# ESP32_Power.net
KiCad netlist of a schematic drawn in Altium Designer
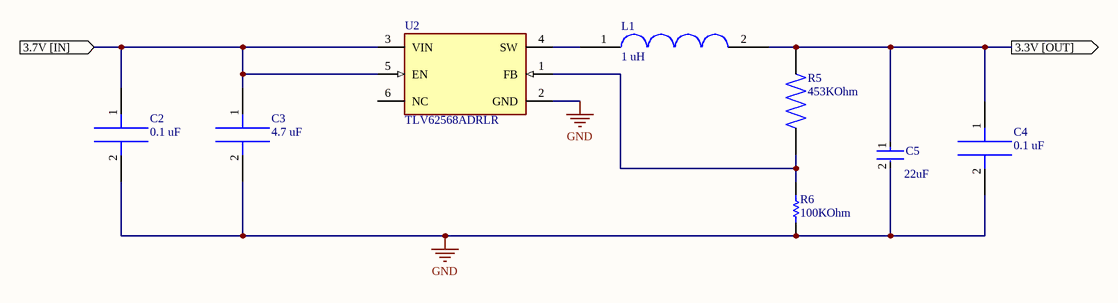
[diagram p0: ESP32 Power.SchDoc]

(export (version "E")
  (design (tool "Eeschema 10.0.6"))
  (components
    (comp (ref "C2")
      (value "0.1 uF")
      (footprint "1206 Capacitor")
      (description "0.1 µF ±10% 6.3V Ceramic Capacitor X7R 1206 (3216 Metric)")
      (fields (field (name "Comment") "GMC31X7R104K6R3NT"))
      (libsource (lib "Team54_Parts") (part "GMC31X7R104K6R3NT"))
    )
    (comp (ref "C3")
      (value "4.7 uF")
      (footprint "12101C47")
      (description "CAP CER 4.7UF 100V X7R 1210")
      (fields (field (name "Comment") "12101C475K4T2A"))
      (libsource (lib "Team54_Parts") (part "12101C47"))
    )
    (comp (ref "C4")
      (value "0.1 uF")
      (footprint "1206 Capacitor")
      (description "0.1 µF ±10% 6.3V Ceramic Capacitor X7R 1206 (3216 Metric)")
      (fields (field (name "Comment") "GMC31X7R104K6R3NT"))
      (libsource (lib "Team54_Parts") (part "GMC31X7R104K6R3NT"))
    )
    (comp (ref "C5")
      (value "GRM21BR60J226ME39L")
      (footprint "FP-GRM21B-0_15-MFG")
      (description "Chip Multilayer Ceramic Capacitors for General Purpose, 0805, 22uF, X5R, 15%, 20%, 6.3V")
      (fields
        (field (name "VOLTAGE") "6.3V")
        (field (name "TOLERANCE") "20%")
        (field (name "CAPACITANCE") "22uF")
      )
      (libsource (lib "Altium Content Vault") (part "b4654b650e69147ec39a6b967a45e02"))
    )
    (comp (ref "L1")
      (value "1 uH")
      (footprint "TYA40121R0M-10")
      (description "TYA40121R0M-10, FIXED IND 1UH 3A 59 MOHM SMD")
      (libsource (lib "Team54_Parts") (part "TYA40121R0M-10"))
    )
    (comp (ref "R5")
      (value "453KOhm")
      (footprint "RES_ERJP14F4533U")
      (description "ERJP14F4533U")
      (libsource (lib "ERJP14F4533U") (part "ERJP14F4533U"))
    )
    (comp (ref "R6")
      (value "RC1206FR-07100KL")
      (footprint "RESC3116X65X40ML10T20")
      (description "Chip Resistor, 100 KOhm, +/- 1%, 0.25 W, -55 to 155 degC, 1206 (3216 Metric), RoHS, Tape and Reel")
      (fields
        (field (name "RESISTANCE") "100KOhm")
        (field (name "TOLERANCE") "1%")
        (field (name "MANUFACTURER") "Yageo")
      )
      (libsource (lib "Altium Content Vault") (part "RES-2"))
    )
    (comp (ref "U2")
      (value "TLV62568ADRLR")
      (footprint "FP-DRL0006A-MFG")
      (description "IC REG BUCK ADJUSTABLE 2A SOT563")
      (libsource (lib "Altium Content Vault") (part "c065b8f3016c1e0e14a773cb518fcf3"))
    )
  )
  (nets
    (net (code "1") (name "/3.3V [OUT]") (class "Default")
      (node (ref "C4") (pin "1") (pinfunction "1_1") (pintype "passive"))
      (node (ref "C5") (pin "1") (pinfunction "1_1") (pintype "passive"))
      (node (ref "L1") (pin "2") (pinfunction "2_2") (pintype "passive"))
      (node (ref "R5") (pin "2") (pinfunction "2_2") (pintype "passive"))
    )
    (net (code "2") (name "/3.7V [IN]") (class "Default")
      (node (ref "C2") (pin "1") (pinfunction "1_1") (pintype "passive"))
      (node (ref "C3") (pin "1") (pinfunction "1_1") (pintype "passive"))
      (node (ref "U2") (pin "3") (pinfunction "VIN_3") (pintype "power_in"))
      (node (ref "U2") (pin "5") (pinfunction "EN_5") (pintype "input"))
    )
    (net (code "3") (name "GND") (class "Default")
      (node (ref "C2") (pin "2") (pinfunction "2_2") (pintype "passive"))
      (node (ref "C3") (pin "2") (pinfunction "2_2") (pintype "passive"))
      (node (ref "C4") (pin "2") (pinfunction "2_2") (pintype "passive"))
      (node (ref "C5") (pin "2") (pinfunction "2_2") (pintype "passive"))
      (node (ref "R6") (pin "1") (pinfunction "1_1") (pintype "passive"))
      (node (ref "U2") (pin "2") (pinfunction "GND_2") (pintype "power_in"))
    )
    (net (code "4") (name "Net-(U2-FB)") (class "Default")
      (node (ref "R5") (pin "1") (pinfunction "1_1") (pintype "passive"))
      (node (ref "R6") (pin "2") (pinfunction "2_2") (pintype "passive"))
      (node (ref "U2") (pin "1") (pinfunction "FB_1") (pintype "input"))
    )
    (net (code "5") (name "Net-(U2-SW)") (class "Default")
      (node (ref "L1") (pin "1") (pinfunction "1_1") (pintype "passive"))
      (node (ref "U2") (pin "4") (pinfunction "SW_4") (pintype "passive"))
    )
    (net (code "6") (name "unconnected-(U2-NC-Pad6)") (class "Default")
      (node (ref "U2") (pin "6") (pinfunction "NC_6") (pintype "passive"))
    )
  )
)
